# EurocardModule.net
KiCad netlist of a schematic drawn in EAGLE
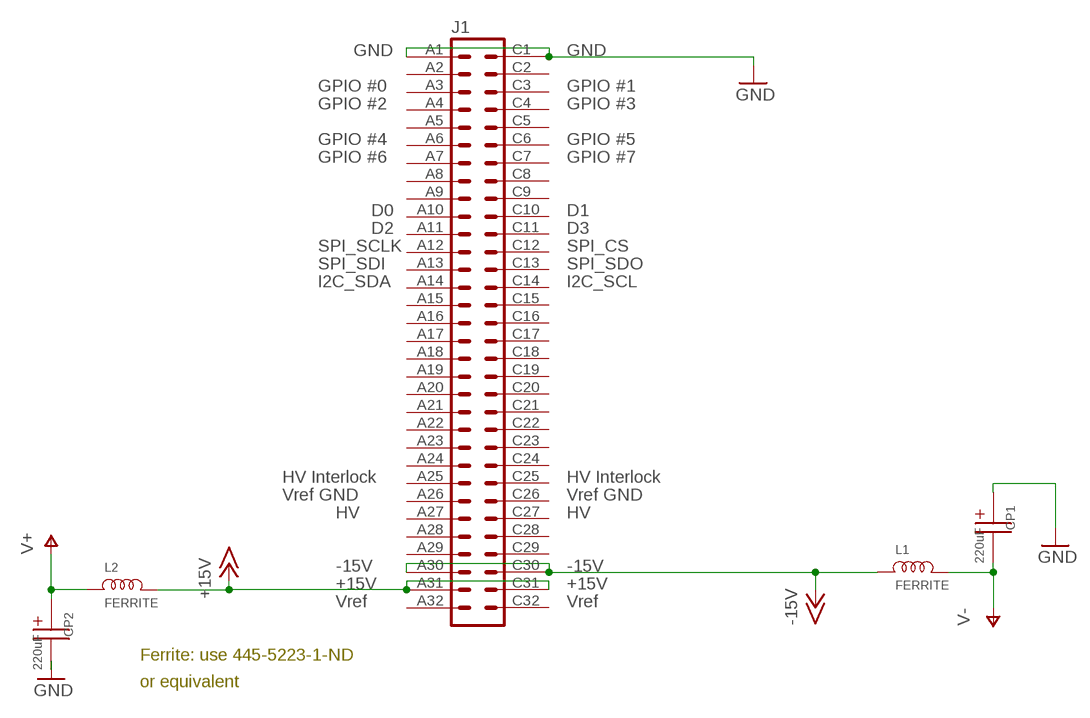
[diagram p0: schematic, sheet 1]

(export (version "E")
  (design (tool "Eeschema 10.0.6"))
  (components
    (comp (ref "CP1")
      (value "220uF")
      (footprint "eagle-import:PANASONIC_F")
      (libsource (lib "eagle-import") (part "CAP-POLPANASONIC_F"))
    )
    (comp (ref "CP2")
      (value "220uF")
      (footprint "eagle-import:PANASONIC_F")
      (libsource (lib "eagle-import") (part "CAP-POLPANASONIC_F"))
    )
    (comp (ref "J1")
      (value "VG64P")
      (footprint "eagle-import:VG64P")
      (libsource (lib "eagle-import") (part "VG64P"))
    )
    (comp (ref "L1")
      (value "FERRITE")
      (footprint "eagle-import:0805")
      (fields (field (name "PARTNO") "445-5223-1-ND"))
      (libsource (lib "eagle-import") (part "INDUCTOR-0805"))
    )
    (comp (ref "L2")
      (value "FERRITE")
      (footprint "eagle-import:0805")
      (fields (field (name "PARTNO") "445-5223-1-ND"))
      (libsource (lib "eagle-import") (part "INDUCTOR-0805"))
    )
  )
  (nets
    (net (code "1") (name "+15V") (class "Default")
      (node (ref "J1") (pin "A31") (pinfunction "A31_A31") (pintype "passive"))
      (node (ref "J1") (pin "C31") (pinfunction "C31_C31") (pintype "passive"))
      (node (ref "L2") (pin "2") (pinfunction "P$2_2") (pintype "passive"))
    )
    (net (code "2") (name "-15V") (class "Default")
      (node (ref "J1") (pin "A30") (pinfunction "A30_A30") (pintype "passive"))
      (node (ref "J1") (pin "C30") (pinfunction "C30_C30") (pintype "passive"))
      (node (ref "L1") (pin "1") (pinfunction "P$1_1") (pintype "passive"))
    )
    (net (code "3") (name "GND") (class "Default")
      (node (ref "CP1") (pin "+") (pinfunction "P$1_+") (pintype "passive"))
      (node (ref "CP2") (pin "-") (pinfunction "P$2_-") (pintype "passive"))
      (node (ref "J1") (pin "A1") (pinfunction "A1_A1") (pintype "passive"))
      (node (ref "J1") (pin "C1") (pinfunction "C1_C1") (pintype "passive"))
    )
    (net (code "4") (name "V+") (class "Default")
      (node (ref "CP2") (pin "+") (pinfunction "P$1_+") (pintype "passive"))
      (node (ref "L2") (pin "1") (pinfunction "P$1_1") (pintype "passive"))
    )
    (net (code "5") (name "V-") (class "Default")
      (node (ref "CP1") (pin "-") (pinfunction "P$2_-") (pintype "passive"))
      (node (ref "L1") (pin "2") (pinfunction "P$2_2") (pintype "passive"))
    )
    (net (code "6") (name "unconnected-(J1-PadA2)") (class "Default")
      (node (ref "J1") (pin "A2") (pinfunction "A2_A2") (pintype "passive"))
    )
    (net (code "7") (name "unconnected-(J1-PadA3)") (class "Default")
      (node (ref "J1") (pin "A3") (pinfunction "A3_A3") (pintype "passive"))
    )
    (net (code "8") (name "unconnected-(J1-PadA4)") (class "Default")
      (node (ref "J1") (pin "A4") (pinfunction "A4_A4") (pintype "passive"))
    )
    (net (code "9") (name "unconnected-(J1-PadA5)") (class "Default")
      (node (ref "J1") (pin "A5") (pinfunction "A5_A5") (pintype "passive"))
    )
    (net (code "10") (name "unconnected-(J1-PadA6)") (class "Default")
      (node (ref "J1") (pin "A6") (pinfunction "A6_A6") (pintype "passive"))
    )
    (net (code "11") (name "unconnected-(J1-PadA7)") (class "Default")
      (node (ref "J1") (pin "A7") (pinfunction "A7_A7") (pintype "passive"))
    )
    (net (code "12") (name "unconnected-(J1-PadA8)") (class "Default")
      (node (ref "J1") (pin "A8") (pinfunction "A8_A8") (pintype "passive"))
    )
    (net (code "13") (name "unconnected-(J1-PadA9)") (class "Default")
      (node (ref "J1") (pin "A9") (pinfunction "A9_A9") (pintype "passive"))
    )
    (net (code "14") (name "unconnected-(J1-PadA10)") (class "Default")
      (node (ref "J1") (pin "A10") (pinfunction "A10_A10") (pintype "passive"))
    )
    (net (code "15") (name "unconnected-(J1-PadA11)") (class "Default")
      (node (ref "J1") (pin "A11") (pinfunction "A11_A11") (pintype "passive"))
    )
    (net (code "16") (name "unconnected-(J1-PadA12)") (class "Default")
      (node (ref "J1") (pin "A12") (pinfunction "A12_A12") (pintype "passive"))
    )
    (net (code "17") (name "unconnected-(J1-PadA13)") (class "Default")
      (node (ref "J1") (pin "A13") (pinfunction "A13_A13") (pintype "passive"))
    )
    (net (code "18") (name "unconnected-(J1-PadA14)") (class "Default")
      (node (ref "J1") (pin "A14") (pinfunction "A14_A14") (pintype "passive"))
    )
    (net (code "19") (name "unconnected-(J1-PadA15)") (class "Default")
      (node (ref "J1") (pin "A15") (pinfunction "A15_A15") (pintype "passive"))
    )
    (net (code "20") (name "unconnected-(J1-PadA16)") (class "Default")
      (node (ref "J1") (pin "A16") (pinfunction "A16_A16") (pintype "passive"))
    )
    (net (code "21") (name "unconnected-(J1-PadA17)") (class "Default")
      (node (ref "J1") (pin "A17") (pinfunction "A17_A17") (pintype "passive"))
    )
    (net (code "22") (name "unconnected-(J1-PadA18)") (class "Default")
      (node (ref "J1") (pin "A18") (pinfunction "A18_A18") (pintype "passive"))
    )
    (net (code "23") (name "unconnected-(J1-PadA19)") (class "Default")
      (node (ref "J1") (pin "A19") (pinfunction "A19_A19") (pintype "passive"))
    )
    (net (code "24") (name "unconnected-(J1-PadA20)") (class "Default")
      (node (ref "J1") (pin "A20") (pinfunction "A20_A20") (pintype "passive"))
    )
    (net (code "25") (name "unconnected-(J1-PadA21)") (class "Default")
      (node (ref "J1") (pin "A21") (pinfunction "A21_A21") (pintype "passive"))
    )
    (net (code "26") (name "unconnected-(J1-PadA22)") (class "Default")
      (node (ref "J1") (pin "A22") (pinfunction "A22_A22") (pintype "passive"))
    )
    (net (code "27") (name "unconnected-(J1-PadA23)") (class "Default")
      (node (ref "J1") (pin "A23") (pinfunction "A23_A23") (pintype "passive"))
    )
    (net (code "28") (name "unconnected-(J1-PadA24)") (class "Default")
      (node (ref "J1") (pin "A24") (pinfunction "A24_A24") (pintype "passive"))
    )
    (net (code "29") (name "unconnected-(J1-PadA25)") (class "Default")
      (node (ref "J1") (pin "A25") (pinfunction "A25_A25") (pintype "passive"))
    )
    (net (code "30") (name "unconnected-(J1-PadA26)") (class "Default")
      (node (ref "J1") (pin "A26") (pinfunction "A26_A26") (pintype "passive"))
    )
    (net (code "31") (name "unconnected-(J1-PadA27)") (class "Default")
      (node (ref "J1") (pin "A27") (pinfunction "A27_A27") (pintype "passive"))
    )
    (net (code "32") (name "unconnected-(J1-PadA28)") (class "Default")
      (node (ref "J1") (pin "A28") (pinfunction "A28_A28") (pintype "passive"))
    )
    (net (code "33") (name "unconnected-(J1-PadA29)") (class "Default")
      (node (ref "J1") (pin "A29") (pinfunction "A29_A29") (pintype "passive"))
    )
    (net (code "34") (name "unconnected-(J1-PadA32)") (class "Default")
      (node (ref "J1") (pin "A32") (pinfunction "A32_A32") (pintype "passive"))
    )
    (net (code "35") (name "unconnected-(J1-PadC2)") (class "Default")
      (node (ref "J1") (pin "C2") (pinfunction "C2_C2") (pintype "passive"))
    )
    (net (code "36") (name "unconnected-(J1-PadC3)") (class "Default")
      (node (ref "J1") (pin "C3") (pinfunction "C3_C3") (pintype "passive"))
    )
    (net (code "37") (name "unconnected-(J1-PadC4)") (class "Default")
      (node (ref "J1") (pin "C4") (pinfunction "C4_C4") (pintype "passive"))
    )
    (net (code "38") (name "unconnected-(J1-PadC5)") (class "Default")
      (node (ref "J1") (pin "C5") (pinfunction "C5_C5") (pintype "passive"))
    )
    (net (code "39") (name "unconnected-(J1-PadC6)") (class "Default")
      (node (ref "J1") (pin "C6") (pinfunction "C6_C6") (pintype "passive"))
    )
    (net (code "40") (name "unconnected-(J1-PadC7)") (class "Default")
      (node (ref "J1") (pin "C7") (pinfunction "C7_C7") (pintype "passive"))
    )
    (net (code "41") (name "unconnected-(J1-PadC8)") (class "Default")
      (node (ref "J1") (pin "C8") (pinfunction "C8_C8") (pintype "passive"))
    )
    (net (code "42") (name "unconnected-(J1-PadC9)") (class "Default")
      (node (ref "J1") (pin "C9") (pinfunction "C9_C9") (pintype "passive"))
    )
    (net (code "43") (name "unconnected-(J1-PadC10)") (class "Default")
      (node (ref "J1") (pin "C10") (pinfunction "C10_C10") (pintype "passive"))
    )
    (net (code "44") (name "unconnected-(J1-PadC11)") (class "Default")
      (node (ref "J1") (pin "C11") (pinfunction "C11_C11") (pintype "passive"))
    )
    (net (code "45") (name "unconnected-(J1-PadC12)") (class "Default")
      (node (ref "J1") (pin "C12") (pinfunction "C12_C12") (pintype "passive"))
    )
    (net (code "46") (name "unconnected-(J1-PadC13)") (class "Default")
      (node (ref "J1") (pin "C13") (pinfunction "C13_C13") (pintype "passive"))
    )
    (net (code "47") (name "unconnected-(J1-PadC14)") (class "Default")
      (node (ref "J1") (pin "C14") (pinfunction "C14_C14") (pintype "passive"))
    )
    (net (code "48") (name "unconnected-(J1-PadC15)") (class "Default")
      (node (ref "J1") (pin "C15") (pinfunction "C15_C15") (pintype "passive"))
    )
    (net (code "49") (name "unconnected-(J1-PadC16)") (class "Default")
      (node (ref "J1") (pin "C16") (pinfunction "C16_C16") (pintype "passive"))
    )
    (net (code "50") (name "unconnected-(J1-PadC17)") (class "Default")
      (node (ref "J1") (pin "C17") (pinfunction "C17_C17") (pintype "passive"))
    )
    (net (code "51") (name "unconnected-(J1-PadC18)") (class "Default")
      (node (ref "J1") (pin "C18") (pinfunction "C18_C18") (pintype "passive"))
    )
    (net (code "52") (name "unconnected-(J1-PadC19)") (class "Default")
      (node (ref "J1") (pin "C19") (pinfunction "C19_C19") (pintype "passive"))
    )
    (net (code "53") (name "unconnected-(J1-PadC20)") (class "Default")
      (node (ref "J1") (pin "C20") (pinfunction "C20_C20") (pintype "passive"))
    )
    (net (code "54") (name "unconnected-(J1-PadC21)") (class "Default")
      (node (ref "J1") (pin "C21") (pinfunction "C21_C21") (pintype "passive"))
    )
    (net (code "55") (name "unconnected-(J1-PadC22)") (class "Default")
      (node (ref "J1") (pin "C22") (pinfunction "C22_C22") (pintype "passive"))
    )
    (net (code "56") (name "unconnected-(J1-PadC23)") (class "Default")
      (node (ref "J1") (pin "C23") (pinfunction "C23_C23") (pintype "passive"))
    )
    (net (code "57") (name "unconnected-(J1-PadC24)") (class "Default")
      (node (ref "J1") (pin "C24") (pinfunction "C24_C24") (pintype "passive"))
    )
    (net (code "58") (name "unconnected-(J1-PadC25)") (class "Default")
      (node (ref "J1") (pin "C25") (pinfunction "C25_C25") (pintype "passive"))
    )
    (net (code "59") (name "unconnected-(J1-PadC26)") (class "Default")
      (node (ref "J1") (pin "C26") (pinfunction "C26_C26") (pintype "passive"))
    )
    (net (code "60") (name "unconnected-(J1-PadC27)") (class "Default")
      (node (ref "J1") (pin "C27") (pinfunction "C27_C27") (pintype "passive"))
    )
    (net (code "61") (name "unconnected-(J1-PadC28)") (class "Default")
      (node (ref "J1") (pin "C28") (pinfunction "C28_C28") (pintype "passive"))
    )
    (net (code "62") (name "unconnected-(J1-PadC29)") (class "Default")
      (node (ref "J1") (pin "C29") (pinfunction "C29_C29") (pintype "passive"))
    )
    (net (code "63") (name "unconnected-(J1-PadC32)") (class "Default")
      (node (ref "J1") (pin "C32") (pinfunction "C32_C32") (pintype "passive"))
    )
  )
)
